# AutoProgramCircuit.net
KiCad netlist of a schematic drawn in Altium Designer
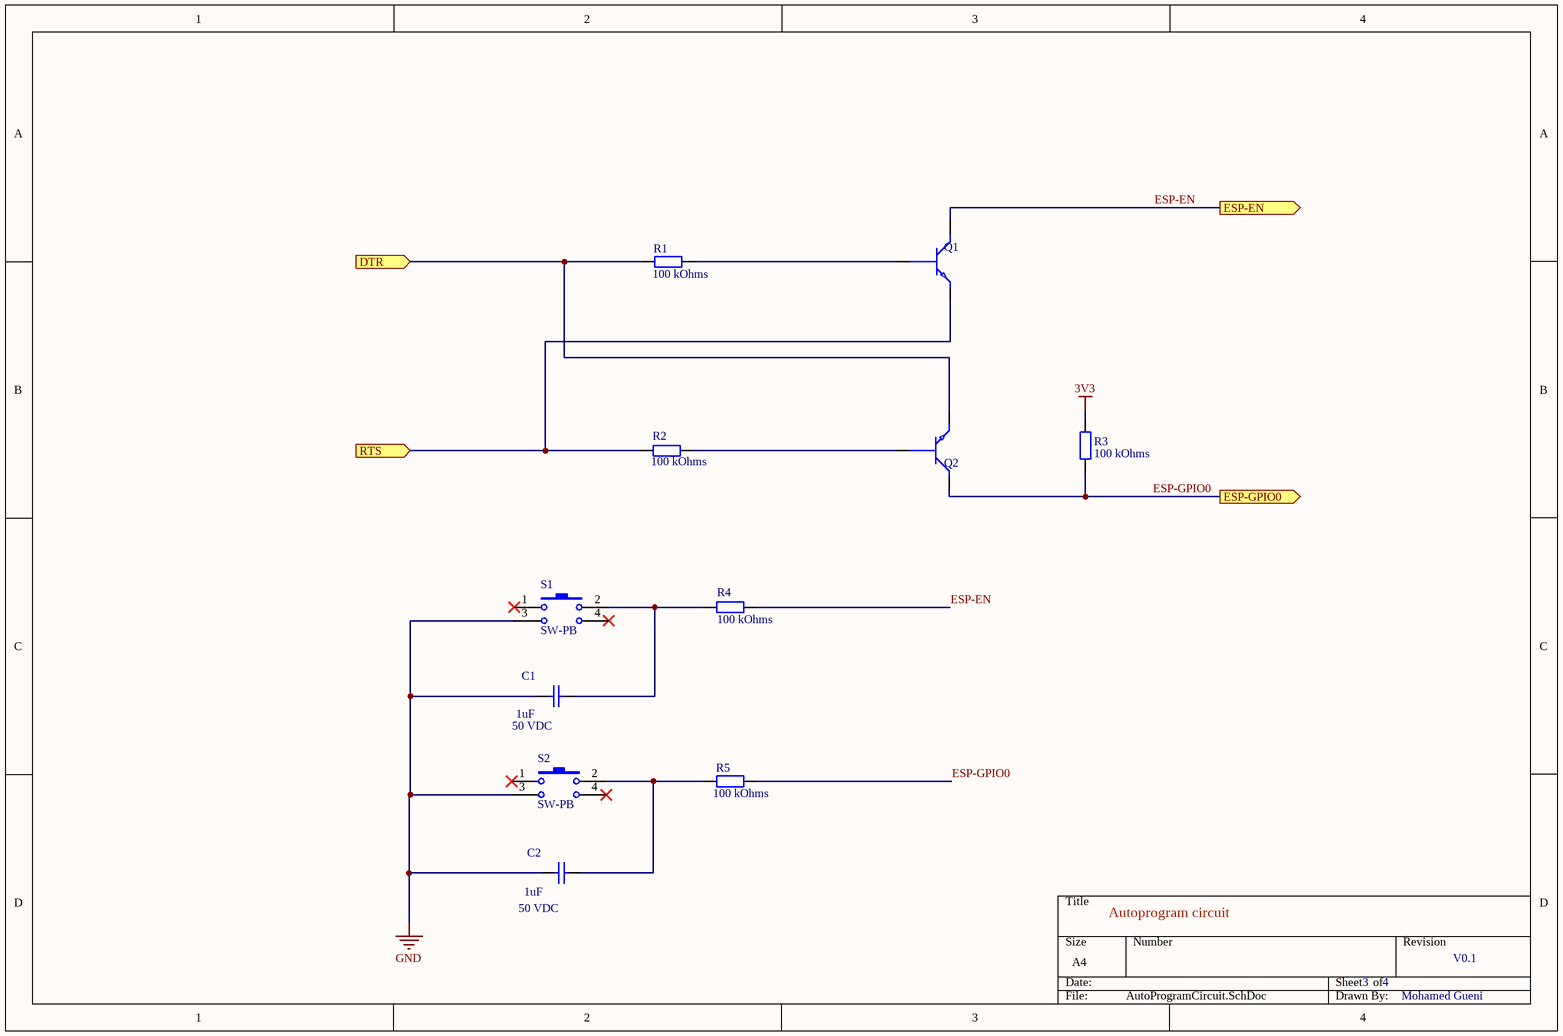
[diagram p0: AutoProgramCircuit.SchDoc]

(export (version "E")
  (design (tool "Eeschema 10.0.6"))
  (components
    (comp (ref "C1")
      (value "Capacitor")
      (footprint "CAP-0603")
      (fields
        (field (name "VALUE 1") "1uF")
        (field (name "VALUE 2") "50 VDC")
        (field (name "PART NUMBER") "C-000000011")
      )
      (libsource (lib "DATABASE") (part "Capacitor"))
    )
    (comp (ref "C2")
      (value "Capacitor")
      (footprint "CAP-0603")
      (fields
        (field (name "VALUE 1") "1uF")
        (field (name "VALUE 2") "50 VDC")
        (field (name "PART NUMBER") "C-000000011")
      )
      (libsource (lib "DATABASE") (part "Capacitor"))
    )
    (comp (ref "Q1")
      (value "BJT")
      (footprint "SOT95P245X112-3N")
      (fields (field (name "PART NUMBER") "Q-000000003"))
      (libsource (lib "DATABASE") (part "BJT"))
    )
    (comp (ref "Q2")
      (value "BJT")
      (footprint "SOT95P245X112-3N")
      (fields (field (name "PART NUMBER") "Q-000000003"))
      (libsource (lib "DATABASE") (part "BJT"))
    )
    (comp (ref "R1")
      (value "Resistor")
      (footprint "R0603")
      (fields (field (name "VALUE 1") "100 kOhms") (field (name "PART NUMBER") "R-000000002"))
      (libsource (lib "") (part "Resistor_1"))
    )
    (comp (ref "R2")
      (value "Resistor")
      (footprint "R0603")
      (fields (field (name "VALUE 1") "100 kOhms") (field (name "PART NUMBER") "R-000000002"))
      (libsource (lib "") (part "Resistor_1"))
    )
    (comp (ref "R3")
      (value "Resistor")
      (footprint "R0603")
      (fields (field (name "VALUE 1") "100 kOhms") (field (name "PART NUMBER") "R-000000002"))
      (libsource (lib "DATABASE") (part "Resistor"))
    )
    (comp (ref "R4")
      (value "Resistor")
      (footprint "R0603")
      (fields (field (name "VALUE 1") "100 kOhms") (field (name "PART NUMBER") "R-000000002"))
      (libsource (lib "") (part "Resistor_1"))
    )
    (comp (ref "R5")
      (value "Resistor")
      (footprint "R0603")
      (fields (field (name "VALUE 1") "100 kOhms") (field (name "PART NUMBER") "R-000000002"))
      (libsource (lib "") (part "Resistor_1"))
    )
    (comp (ref "S1") (value "SW-PB") (footprint "SKHHDHA010") (libsource (lib "DATABASE") (part "SW-PB")))
    (comp (ref "S2") (value "SW-PB") (footprint "SKHHDHA010") (libsource (lib "DATABASE") (part "SW-PB")))
  )
  (nets
    (net (code "1") (name "/DTR") (class "Default")
      (node (ref "Q2") (pin "2") (pinfunction "E_2") (pintype "passive"))
      (node (ref "R1") (pin "1") (pinfunction "1_1") (pintype "passive"))
    )
    (net (code "2") (name "/ESP-EN") (class "Default")
      (node (ref "Q1") (pin "3") (pinfunction "C_3") (pintype "passive"))
      (node (ref "R4") (pin "2") (pinfunction "2_2") (pintype "passive"))
    )
    (net (code "3") (name "/ESP-GPIO0") (class "Default")
      (node (ref "Q2") (pin "3") (pinfunction "C_3") (pintype "passive"))
      (node (ref "R3") (pin "1") (pinfunction "1_1") (pintype "passive"))
      (node (ref "R5") (pin "2") (pinfunction "2_2") (pintype "passive"))
    )
    (net (code "4") (name "/RTS") (class "Default")
      (node (ref "Q1") (pin "2") (pinfunction "E_2") (pintype "passive"))
      (node (ref "R2") (pin "1") (pinfunction "1_1") (pintype "passive"))
    )
    (net (code "5") (name "3V3") (class "Default")
      (node (ref "R3") (pin "2") (pinfunction "2_2") (pintype "passive"))
    )
    (net (code "6") (name "GND") (class "Default")
      (node (ref "C1") (pin "1") (pinfunction "1_1") (pintype "passive"))
      (node (ref "C2") (pin "1") (pinfunction "1_1") (pintype "passive"))
      (node (ref "S1") (pin "3") (pinfunction "3_3") (pintype "passive"))
      (node (ref "S2") (pin "3") (pinfunction "3_3") (pintype "passive"))
    )
    (net (code "7") (name "Net-(C1-Pad2)") (class "Default")
      (node (ref "C1") (pin "2") (pinfunction "2_2") (pintype "passive"))
      (node (ref "R4") (pin "1") (pinfunction "1_1") (pintype "passive"))
      (node (ref "S1") (pin "2") (pinfunction "2_2") (pintype "passive"))
    )
    (net (code "8") (name "Net-(C2-Pad2)") (class "Default")
      (node (ref "C2") (pin "2") (pinfunction "2_2") (pintype "passive"))
      (node (ref "R5") (pin "1") (pinfunction "1_1") (pintype "passive"))
      (node (ref "S2") (pin "2") (pinfunction "2_2") (pintype "passive"))
    )
    (net (code "9") (name "Net-(Q1-B)") (class "Default")
      (node (ref "Q1") (pin "1") (pinfunction "B_1") (pintype "passive"))
      (node (ref "R1") (pin "2") (pinfunction "2_2") (pintype "passive"))
    )
    (net (code "10") (name "Net-(Q2-B)") (class "Default")
      (node (ref "Q2") (pin "1") (pinfunction "B_1") (pintype "passive"))
      (node (ref "R2") (pin "2") (pinfunction "2_2") (pintype "passive"))
    )
    (net (code "11") (name "unconnected-(S1-Pad1)") (class "Default")
      (node (ref "S1") (pin "1") (pinfunction "1_1") (pintype "passive+no_connect"))
    )
    (net (code "12") (name "unconnected-(S1-Pad4)") (class "Default")
      (node (ref "S1") (pin "4") (pinfunction "4_4") (pintype "passive+no_connect"))
    )
    (net (code "13") (name "unconnected-(S2-Pad1)") (class "Default")
      (node (ref "S2") (pin "1") (pinfunction "1_1") (pintype "passive+no_connect"))
    )
    (net (code "14") (name "unconnected-(S2-Pad4)") (class "Default")
      (node (ref "S2") (pin "4") (pinfunction "4_4") (pintype "passive+no_connect"))
    )
  )
)
